# stm32_schematic.net
KiCad netlist of a schematic drawn in Altium Designer
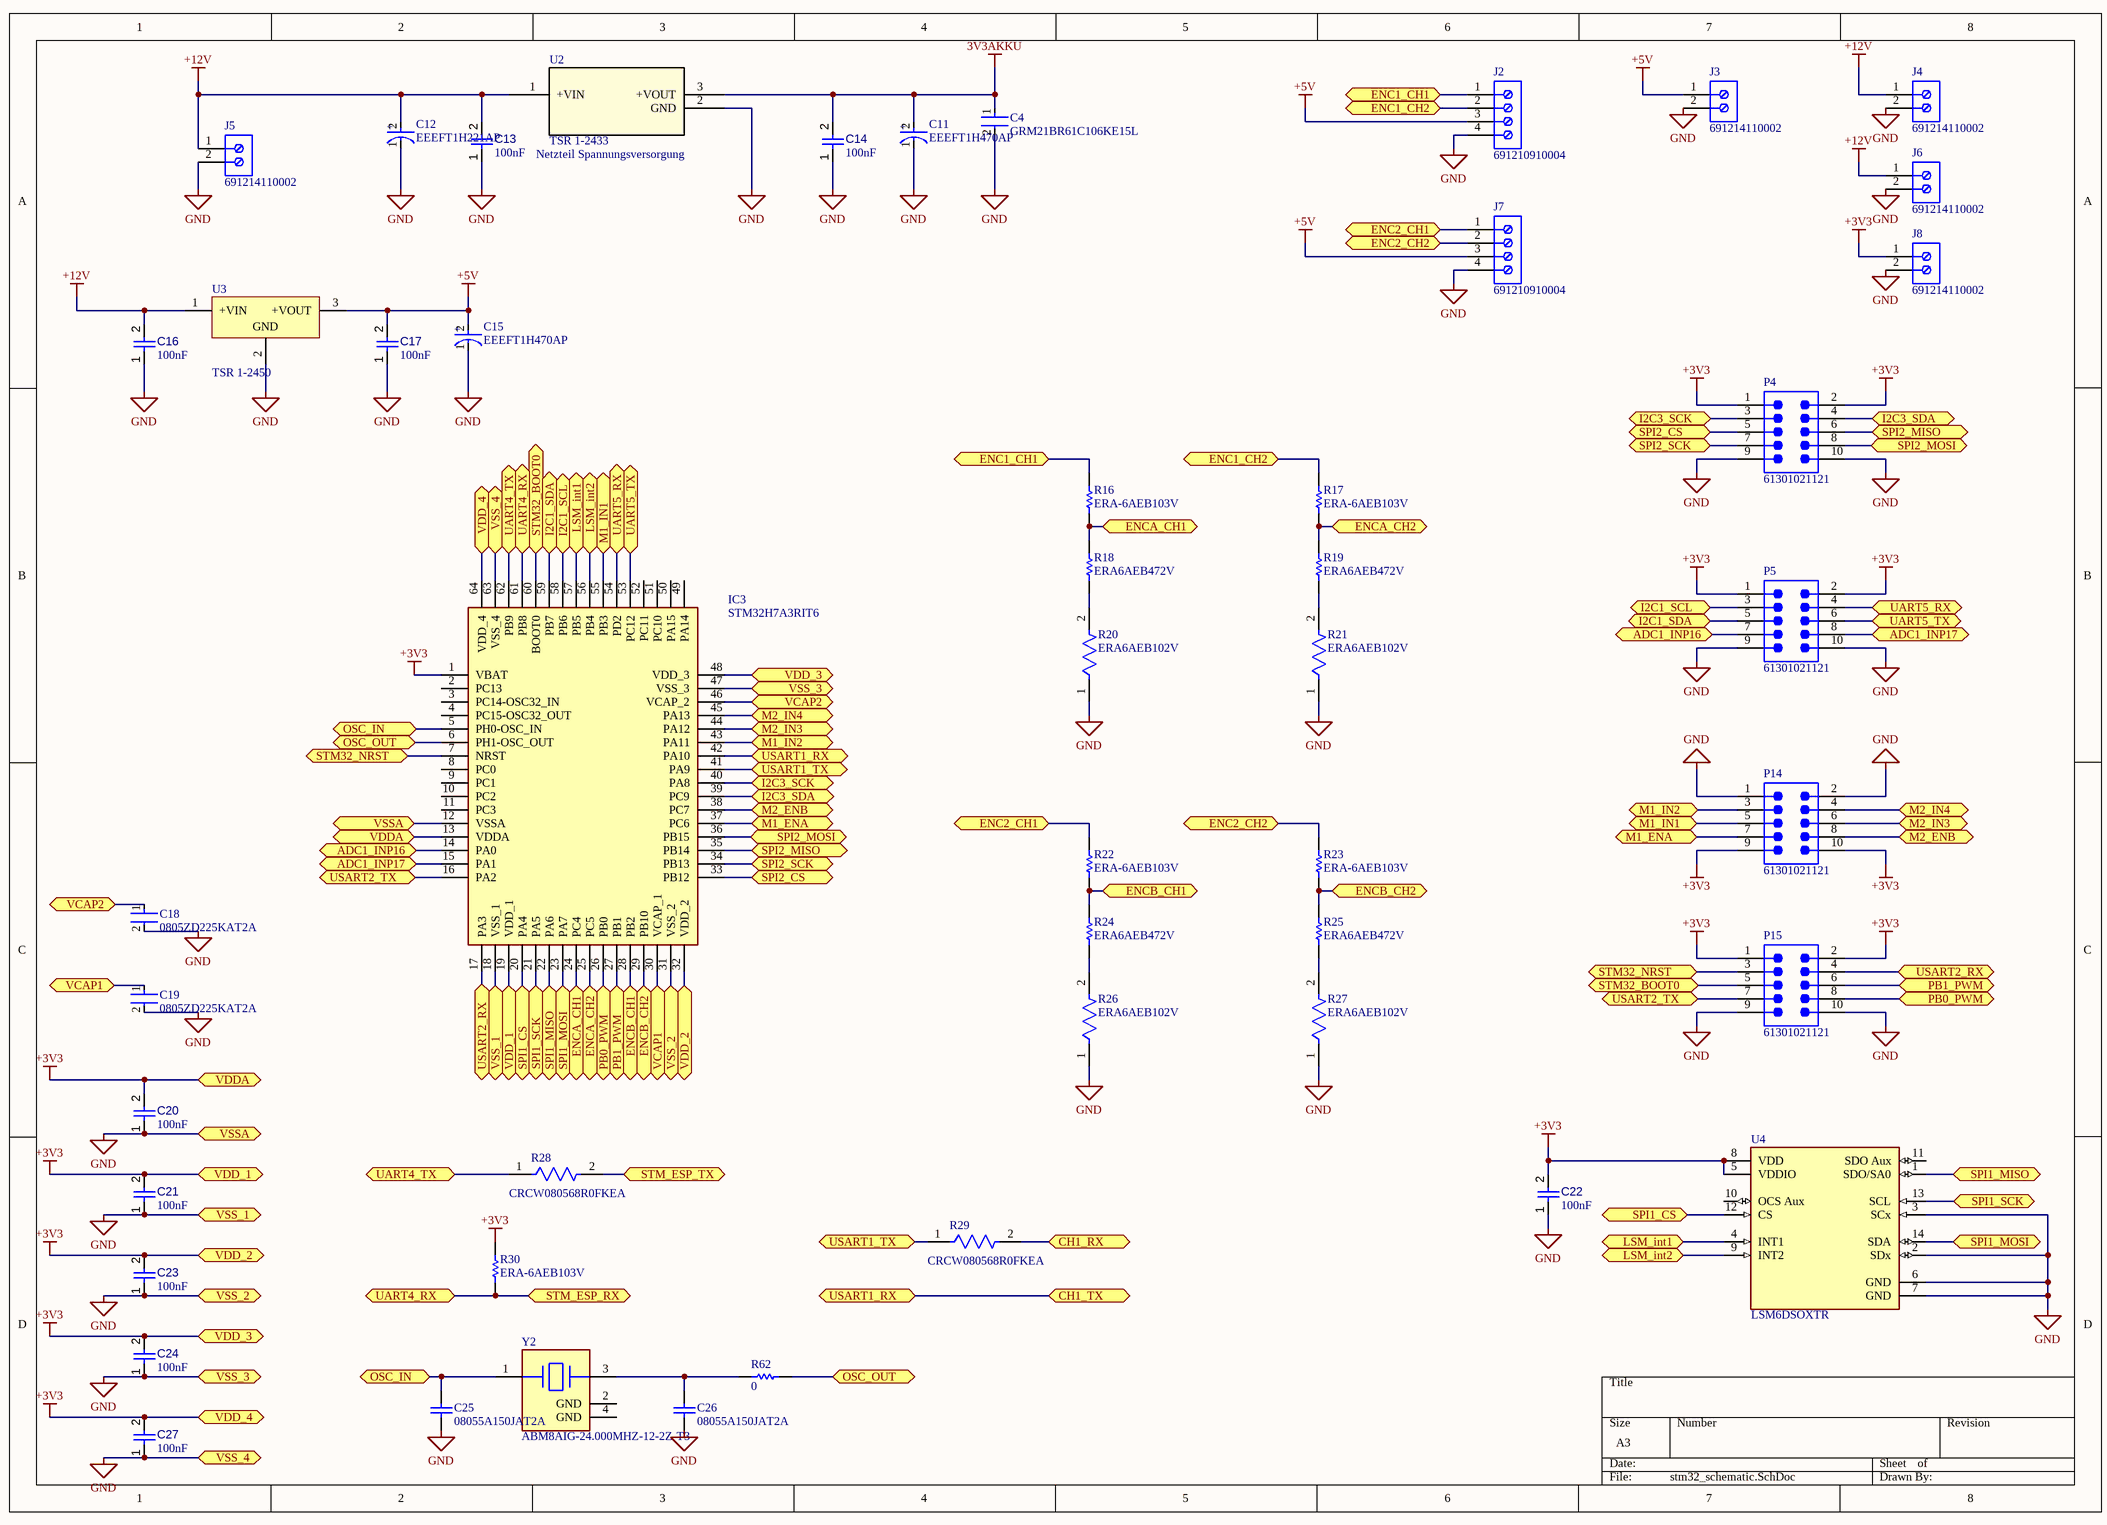
[diagram p0: stm32_schematic.SchDoc]

(export (version "E")
  (design (tool "Eeschema 10.0.6"))
  (components
    (comp (ref "C4")
      (value "GRM21BR61C106KE15L")
      (footprint "FP-GRM21B-0_1-IPC_C")
      (description "Chip Multilayer Ceramic Capacitors for General Purpose, 0805, 10uF, X5R, 15%, 10%, 16V")
      (fields (field (name "TOLERANCE") "10%") (field (name "VOLTAGE") "16V"))
      (libsource (lib "Altium Content Vault") (part "b4654b650e69147ec39a6b967a45e02"))
    )
    (comp (ref "C11")
      (value "EEEFT1H470AP")
      (footprint "FP-FTD-MFG")
      (description "CAP ALUM 47UF 20% 50V SMD")
      (fields (field (name "VOLTAGE") "50V") (field (name "TOLERANCE") "20%"))
      (libsource (lib "Altium Content Vault") (part "a00bbbee19879c290e62620ae7e47b1"))
    )
    (comp (ref "C12")
      (value "EEEFT1H221AP")
      (footprint "FP-FTF-MFG")
      (description "CAP ALUM 220UF 20% 50V SMD")
      (fields (field (name "TOLERANCE") "20%") (field (name "VOLTAGE") "50V"))
      (libsource (lib "Altium Content Vault") (part "203bc49f2ac43e59fd269a8c329ed05"))
    )
    (comp (ref "C13")
      (value "100nF")
      (footprint "CAPC2013X95X50LL10T25")
      (description "Chip Capacitor, 100 nF, +/- 10%, 50 V, 0805 (2012 Metric)")
      (fields (field (name "TOLERANCE") "10%") (field (name "Comment") "Capacitor 100 nF +/-10% 50 V 0805"))
      (libsource (lib "Lennart Götz") (part "CAP-NP-2"))
    )
    (comp (ref "C14")
      (value "100nF")
      (footprint "CAPC2013X95X50LL10T25")
      (description "Chip Capacitor, 100 nF, +/- 10%, 50 V, 0805 (2012 Metric)")
      (fields (field (name "TOLERANCE") "10%") (field (name "Comment") "Capacitor 100 nF +/-10% 50 V 0805"))
      (libsource (lib "Lennart Götz") (part "CAP-NP-2"))
    )
    (comp (ref "C15")
      (value "EEEFT1H470AP")
      (footprint "FP-FTD-MFG")
      (description "CAP ALUM 47UF 20% 50V SMD")
      (fields (field (name "VOLTAGE") "50V") (field (name "TOLERANCE") "20%"))
      (libsource (lib "Altium Content Vault") (part "a00bbbee19879c290e62620ae7e47b1"))
    )
    (comp (ref "C16")
      (value "100nF")
      (footprint "CAPC2013X95X50LL10T25")
      (description "Chip Capacitor, 100 nF, +/- 10%, 50 V, 0805 (2012 Metric)")
      (fields (field (name "TOLERANCE") "10%") (field (name "Comment") "Capacitor 100 nF +/-10% 50 V 0805"))
      (libsource (lib "Lennart Götz") (part "CAP-NP-2"))
    )
    (comp (ref "C17")
      (value "100nF")
      (footprint "CAPC2013X95X50LL10T25")
      (description "Chip Capacitor, 100 nF, +/- 10%, 50 V, 0805 (2012 Metric)")
      (fields (field (name "TOLERANCE") "10%") (field (name "Comment") "Capacitor 100 nF +/-10% 50 V 0805"))
      (libsource (lib "Lennart Götz") (part "CAP-NP-2"))
    )
    (comp (ref "C18")
      (value "0805ZD225KAT2A")
      (footprint "FP-0805-L_2_01_0_2-W_1_25-IPC_B")
      (description "General Purpose Ceramic Capacitor, 0805, 2.2uF, 10%, X5R, 15%, 10V")
      (fields (field (name "VOLTAGE") "10V") (field (name "TOLERANCE") "10%"))
      (libsource (lib "Altium Content Vault") (part "b4654b650e69147ec39a6b967a45e02"))
    )
    (comp (ref "C19")
      (value "0805ZD225KAT2A")
      (footprint "FP-0805-L_2_01_0_2-W_1_25-IPC_B")
      (description "General Purpose Ceramic Capacitor, 0805, 2.2uF, 10%, X5R, 15%, 10V")
      (fields (field (name "VOLTAGE") "10V") (field (name "TOLERANCE") "10%"))
      (libsource (lib "Altium Content Vault") (part "b4654b650e69147ec39a6b967a45e02"))
    )
    (comp (ref "C20")
      (value "100nF")
      (footprint "CAPC2013X95X50LL10T25")
      (description "Chip Capacitor, 100 nF, +/- 10%, 50 V, 0805 (2012 Metric)")
      (fields (field (name "TOLERANCE") "10%") (field (name "Comment") "Capacitor 100 nF +/-10% 50 V 0805"))
      (libsource (lib "Lennart Götz") (part "CAP-NP-2"))
    )
    (comp (ref "C21")
      (value "100nF")
      (footprint "CAPC2013X95X50LL10T25")
      (description "Chip Capacitor, 100 nF, +/- 10%, 50 V, 0805 (2012 Metric)")
      (fields (field (name "TOLERANCE") "10%") (field (name "Comment") "Capacitor 100 nF +/-10% 50 V 0805"))
      (libsource (lib "Lennart Götz") (part "CAP-NP-2"))
    )
    (comp (ref "C22")
      (value "100nF")
      (footprint "CAPC2013X95X50LL10T25")
      (description "Chip Capacitor, 100 nF, +/- 10%, 50 V, 0805 (2012 Metric)")
      (fields (field (name "TOLERANCE") "10%") (field (name "Comment") "Capacitor 100 nF +/-10% 50 V 0805"))
      (libsource (lib "Lennart Götz") (part "CAP-NP-2"))
    )
    (comp (ref "C23")
      (value "100nF")
      (footprint "CAPC2013X95X50LL10T25")
      (description "Chip Capacitor, 100 nF, +/- 10%, 50 V, 0805 (2012 Metric)")
      (fields (field (name "TOLERANCE") "10%") (field (name "Comment") "Capacitor 100 nF +/-10% 50 V 0805"))
      (libsource (lib "Lennart Götz") (part "CAP-NP-2"))
    )
    (comp (ref "C24")
      (value "100nF")
      (footprint "CAPC2013X95X50LL10T25")
      (description "Chip Capacitor, 100 nF, +/- 10%, 50 V, 0805 (2012 Metric)")
      (fields (field (name "TOLERANCE") "10%") (field (name "Comment") "Capacitor 100 nF +/-10% 50 V 0805"))
      (libsource (lib "Lennart Götz") (part "CAP-NP-2"))
    )
    (comp (ref "C25")
      (value "08055A150JAT2A")
      (footprint "CAPC2013X140X50LL20T25")
      (fields (field (name "MANUFACTURER") "AVX Interconnect / Elco"))
      (libsource (lib "Altium Content Vault") (part "CAP"))
    )
    (comp (ref "C26")
      (value "08055A150JAT2A")
      (footprint "CAPC2013X140X50LL20T25")
      (fields (field (name "MANUFACTURER") "AVX Interconnect / Elco"))
      (libsource (lib "Altium Content Vault") (part "CAP"))
    )
    (comp (ref "C27")
      (value "100nF")
      (footprint "CAPC2013X95X50LL10T25")
      (description "Chip Capacitor, 100 nF, +/- 10%, 50 V, 0805 (2012 Metric)")
      (fields (field (name "TOLERANCE") "10%") (field (name "Comment") "Capacitor 100 nF +/-10% 50 V 0805"))
      (libsource (lib "Lennart Götz") (part "CAP-NP-2"))
    )
    (comp (ref "IC3")
      (value "STM32H7A3RIT6")
      (footprint "SamacSys:QFP50P1200X1200X160-64N")
      (description "Integrated Circuit")
      (fields (field (name "MOUSER PART NUMBER") "511-STM32H7A3RIT6"))
      (libsource (lib "*") (part "STM32H7A3RIT6"))
    )
    (comp (ref "J2")
      (value "691210910004")
      (footprint "691210910004")
      (libsource (lib "Altium Content Vault") (part "TBL - 1R - 04P - Screw"))
    )
    (comp (ref "J3")
      (value "691214110002")
      (footprint "691214110002")
      (fields (field (name "VOLTAGE") "300V"))
      (libsource (lib "Altium Content Vault") (part "TBL - 1R - 02P - Screw"))
    )
    (comp (ref "J4")
      (value "691214110002")
      (footprint "691214110002")
      (fields (field (name "VOLTAGE") "300V"))
      (libsource (lib "Altium Content Vault") (part "TBL - 1R - 02P - Screw"))
    )
    (comp (ref "J5")
      (value "691214110002")
      (footprint "691214110002")
      (fields (field (name "VOLTAGE") "300V"))
      (libsource (lib "Altium Content Vault") (part "TBL - 1R - 02P - Screw"))
    )
    (comp (ref "J6")
      (value "691214110002")
      (footprint "691214110002")
      (fields (field (name "VOLTAGE") "300V"))
      (libsource (lib "Altium Content Vault") (part "TBL - 1R - 02P - Screw"))
    )
    (comp (ref "J7")
      (value "691210910004")
      (footprint "691210910004")
      (libsource (lib "Altium Content Vault") (part "TBL - 1R - 04P - Screw"))
    )
    (comp (ref "J8")
      (value "691214110002")
      (footprint "691214110002")
      (fields (field (name "VOLTAGE") "300V"))
      (libsource (lib "Altium Content Vault") (part "TBL - 1R - 02P - Screw"))
    )
    (comp (ref "P4")
      (value "61301021121")
      (footprint "61301021121")
      (libsource (lib "Altium Content Vault") (part "Header_Male_2R_10P"))
    )
    (comp (ref "P5")
      (value "61301021121")
      (footprint "61301021121")
      (libsource (lib "Altium Content Vault") (part "Header_Male_2R_10P"))
    )
    (comp (ref "P14")
      (value "61301021121")
      (footprint "61301021121")
      (libsource (lib "Altium Content Vault") (part "Header_Male_2R_10P"))
    )
    (comp (ref "P15")
      (value "61301021121")
      (footprint "61301021121")
      (libsource (lib "Altium Content Vault") (part "Header_Male_2R_10P"))
    )
    (comp (ref "R16")
      (value "ERA-6AEB103V")
      (footprint "RESC2013X60X40LL20T25_A")
      (fields (field (name "TOLERANCE") "0.1%") (field (name "MANUFACTURER") "Panasonic"))
      (libsource (lib "Altium Content Vault") (part "RES-2"))
    )
    (comp (ref "R17")
      (value "ERA-6AEB103V")
      (footprint "RESC2013X60X40LL20T25_A")
      (fields (field (name "TOLERANCE") "0.1%") (field (name "MANUFACTURER") "Panasonic"))
      (libsource (lib "Altium Content Vault") (part "RES-2"))
    )
    (comp (ref "R18")
      (value "ERA6AEB472V")
      (footprint "RESC2013X60X40ML20T25")
      (fields (field (name "MANUFACTURER") "Panasonic"))
      (libsource (lib "Altium Content Vault") (part "RES"))
    )
    (comp (ref "R19")
      (value "ERA6AEB472V")
      (footprint "RESC2013X60X40ML20T25")
      (fields (field (name "MANUFACTURER") "Panasonic"))
      (libsource (lib "Altium Content Vault") (part "RES"))
    )
    (comp (ref "R20")
      (value "ERA6AEB102V")
      (footprint "FP-ERA6A-IPC_C")
      (description "RES 1K OHM 0.1% 1/8W 0805")
      (fields (field (name "TOLERANCE") "0.1%"))
      (libsource (lib "Altium Content Vault") (part "1029c3af85768c4190bb7ad29bc67b5"))
    )
    (comp (ref "R21")
      (value "ERA6AEB102V")
      (footprint "FP-ERA6A-IPC_C")
      (description "RES 1K OHM 0.1% 1/8W 0805")
      (fields (field (name "TOLERANCE") "0.1%"))
      (libsource (lib "Altium Content Vault") (part "1029c3af85768c4190bb7ad29bc67b5"))
    )
    (comp (ref "R22")
      (value "ERA-6AEB103V")
      (footprint "RESC2013X60X40LL20T25_A")
      (fields (field (name "TOLERANCE") "0.1%") (field (name "MANUFACTURER") "Panasonic"))
      (libsource (lib "Altium Content Vault") (part "RES-2"))
    )
    (comp (ref "R23")
      (value "ERA-6AEB103V")
      (footprint "RESC2013X60X40LL20T25_A")
      (fields (field (name "TOLERANCE") "0.1%") (field (name "MANUFACTURER") "Panasonic"))
      (libsource (lib "Altium Content Vault") (part "RES-2"))
    )
    (comp (ref "R24")
      (value "ERA6AEB472V")
      (footprint "RESC2013X60X40ML20T25")
      (fields (field (name "MANUFACTURER") "Panasonic"))
      (libsource (lib "Altium Content Vault") (part "RES"))
    )
    (comp (ref "R25")
      (value "ERA6AEB472V")
      (footprint "RESC2013X60X40ML20T25")
      (fields (field (name "MANUFACTURER") "Panasonic"))
      (libsource (lib "Altium Content Vault") (part "RES"))
    )
    (comp (ref "R26")
      (value "ERA6AEB102V")
      (footprint "FP-ERA6A-IPC_C")
      (description "RES 1K OHM 0.1% 1/8W 0805")
      (fields (field (name "TOLERANCE") "0.1%"))
      (libsource (lib "Altium Content Vault") (part "1029c3af85768c4190bb7ad29bc67b5"))
    )
    (comp (ref "R27")
      (value "ERA6AEB102V")
      (footprint "FP-ERA6A-IPC_C")
      (description "RES 1K OHM 0.1% 1/8W 0805")
      (fields (field (name "TOLERANCE") "0.1%"))
      (libsource (lib "Altium Content Vault") (part "1029c3af85768c4190bb7ad29bc67b5"))
    )
    (comp (ref "R28")
      (value "CRCW080568R0FKEA")
      (footprint "FP-CRCW0805-e3-IPC_C")
      (description "RES Thick Film, 68Ω, 1%, 0.125W, 100ppm/°C, 0805")
      (fields (field (name "TOLERANCE") "1%"))
      (libsource (lib "Altium Content Vault") (part "1029c3af85768c4190bb7ad29bc67b5"))
    )
    (comp (ref "R29")
      (value "CRCW080568R0FKEA")
      (footprint "FP-CRCW0805-e3-IPC_C")
      (description "RES Thick Film, 68Ω, 1%, 0.125W, 100ppm/°C, 0805")
      (fields (field (name "TOLERANCE") "1%"))
      (libsource (lib "Altium Content Vault") (part "1029c3af85768c4190bb7ad29bc67b5"))
    )
    (comp (ref "R30")
      (value "ERA-6AEB103V")
      (footprint "RESC2013X60X40LL20T25_A")
      (fields (field (name "TOLERANCE") "0.1%") (field (name "MANUFACTURER") "Panasonic"))
      (libsource (lib "Altium Content Vault") (part "RES-2"))
    )
    (comp (ref "R62")
      (value "0")
      (footprint "RESC2013X60X35ML10T20")
      (description "Chip Resistor, 0 Ohm, 0.125 W, -55 to 155 degC, 0805 (2012 Metric)")
      (fields (field (name "POWER") "125mW") (field (name "TOLERANCE") "5%"))
      (libsource (lib "Lennart Götz") (part "RES-2"))
    )
    (comp (ref "U2")
      (value "TSR 1-2433")
      (footprint "TSR1-SINGLE_TRP")
      (libsource (lib "Altium Content Vault") (part "TSR 1-2433"))
    )
    (comp (ref "U3")
      (value "TSR 1-2450")
      (footprint "TRACO-SIP-3_V")
      (description "DC/DC converter, 5 VDC, 1000 mA, -40 to 85 degC, 3-Pin SIP, RoHS")
      (fields (field (name "MANUFACTURER") "Tracopower"))
      (libsource (lib "Altium Content Vault") (part "TRACO-TSR1-2450-SIP-3"))
    )
    (comp (ref "U4")
      (value "LSM6DSOXTR")
      (footprint "FP-LGA-14L-DM00249496-MFG")
      (description "INEMO INERTIAL MODULE: 3D ACCELE")
      (fields
        (field (name "OCTOPART") "https://octopart.com/lsm6dsoxtr-stmicroelectronics-98102600")
        (field (name "MANUFACTURER") "STMicroelectronics")
      )
      (libsource (lib "Altium Content Vault") (part "e907d670a73553dd54601dfd5d274f3"))
    )
    (comp (ref "Y2")
      (value "ABM8AIG-24.000MHZ-12-2Z-T3")
      (footprint "FP-ABM8AIG-MFG")
      (description "Crystal 24MHz ±20ppm (Tol) ±50ppm (Stability) 12pF FUND 50Ω Automotive 4-Pin Ultra Mini-CSMD T/R")
      (libsource (lib "Altium Content Vault") (part "5645ab55de99a04feaa93ac4102b7fe"))
    )
  )
  (nets
    (net (code "1") (name "+3V3") (class "Default")
      (node (ref "C20") (pin "2") (pinfunction "2_2") (pintype "passive"))
      (node (ref "C21") (pin "2") (pinfunction "2_2") (pintype "passive"))
      (node (ref "C22") (pin "2") (pinfunction "2_2") (pintype "passive"))
      (node (ref "C23") (pin "2") (pinfunction "2_2") (pintype "passive"))
      (node (ref "C24") (pin "2") (pinfunction "2_2") (pintype "passive"))
      (node (ref "C27") (pin "2") (pinfunction "2_2") (pintype "passive"))
      (node (ref "IC3") (pin "1") (pinfunction "VBAT_1") (pintype "passive"))
      (node (ref "IC3") (pin "13") (pinfunction "VDDA_13") (pintype "passive"))
      (node (ref "IC3") (pin "19") (pinfunction "VDD_1_19") (pintype "passive"))
      (node (ref "IC3") (pin "32") (pinfunction "VDD_2_32") (pintype "passive"))
      (node (ref "IC3") (pin "48") (pinfunction "VDD_3_48") (pintype "passive"))
      (node (ref "IC3") (pin "64") (pinfunction "VDD_4_64") (pintype "passive"))
      (node (ref "J8") (pin "1") (pinfunction "1_1") (pintype "passive"))
      (node (ref "P14") (pin "10") (pinfunction "10_10") (pintype "passive"))
      (node (ref "P14") (pin "9") (pinfunction "9_9") (pintype "passive"))
      (node (ref "P15") (pin "1") (pinfunction "1_1") (pintype "passive"))
      (node (ref "P15") (pin "2") (pinfunction "2_2") (pintype "passive"))
      (node (ref "P4") (pin "1") (pinfunction "1_1") (pintype "passive"))
      (node (ref "P4") (pin "2") (pinfunction "2_2") (pintype "passive"))
      (node (ref "P5") (pin "1") (pinfunction "1_1") (pintype "passive"))
      (node (ref "P5") (pin "2") (pinfunction "2_2") (pintype "passive"))
      (node (ref "R30") (pin "2") (pinfunction "2_2") (pintype "passive"))
      (node (ref "U4") (pin "5") (pinfunction "VDDIO_5") (pintype "power_in"))
      (node (ref "U4") (pin "8") (pinfunction "VDD_8") (pintype "power_in"))
    )
    (net (code "2") (name "+5V") (class "Default")
      (node (ref "C15") (pin "2") (pinfunction "A_2") (pintype "passive"))
      (node (ref "C17") (pin "2") (pinfunction "2_2") (pintype "passive"))
      (node (ref "J2") (pin "3") (pinfunction "3_3") (pintype "passive"))
      (node (ref "J3") (pin "1") (pinfunction "1_1") (pintype "passive"))
      (node (ref "J7") (pin "3") (pinfunction "3_3") (pintype "passive"))
      (node (ref "U3") (pin "3") (pinfunction "+VOUT_3") (pintype "power_in"))
    )
    (net (code "3") (name "+12V") (class "Default")
      (node (ref "C12") (pin "2") (pinfunction "A_2") (pintype "passive"))
      (node (ref "C13") (pin "2") (pinfunction "2_2") (pintype "passive"))
      (node (ref "C16") (pin "2") (pinfunction "2_2") (pintype "passive"))
      (node (ref "J4") (pin "1") (pinfunction "1_1") (pintype "passive"))
      (node (ref "J5") (pin "1") (pinfunction "1_1") (pintype "passive"))
      (node (ref "J6") (pin "1") (pinfunction "1_1") (pintype "passive"))
      (node (ref "U2") (pin "1") (pinfunction "+VIN_1") (pintype "power_in"))
      (node (ref "U3") (pin "1") (pinfunction "+VIN_1") (pintype "power_in"))
    )
    (net (code "4") (name "/ADC1_INP16") (class "Default")
      (node (ref "IC3") (pin "14") (pinfunction "PA0_14") (pintype "passive"))
      (node (ref "P5") (pin "7") (pinfunction "7_7") (pintype "passive"))
    )
    (net (code "5") (name "/ADC1_INP17") (class "Default")
      (node (ref "IC3") (pin "15") (pinfunction "PA1_15") (pintype "passive"))
      (node (ref "P5") (pin "8") (pinfunction "8_8") (pintype "passive"))
    )
    (net (code "6") (name "/CH1_RX") (class "Default")
      (node (ref "R29") (pin "2") (pinfunction "2_2") (pintype "passive"))
    )
    (net (code "7") (name "/CH1_TX") (class "Default")
      (node (ref "IC3") (pin "42") (pinfunction "PA10_42") (pintype "passive"))
    )
    (net (code "8") (name "/ENC1_CH1") (class "Default")
      (node (ref "J2") (pin "1") (pinfunction "1_1") (pintype "passive"))
      (node (ref "R16") (pin "2") (pinfunction "2_2") (pintype "passive"))
    )
    (net (code "9") (name "/ENC1_CH2") (class "Default")
      (node (ref "J2") (pin "2") (pinfunction "2_2") (pintype "passive"))
      (node (ref "R17") (pin "2") (pinfunction "2_2") (pintype "passive"))
    )
    (net (code "10") (name "/ENC2_CH1") (class "Default")
      (node (ref "J7") (pin "1") (pinfunction "1_1") (pintype "passive"))
      (node (ref "R22") (pin "2") (pinfunction "2_2") (pintype "passive"))
    )
    (net (code "11") (name "/ENC2_CH2") (class "Default")
      (node (ref "J7") (pin "2") (pinfunction "2_2") (pintype "passive"))
      (node (ref "R23") (pin "2") (pinfunction "2_2") (pintype "passive"))
    )
    (net (code "12") (name "/ENCA_CH1") (class "Default")
      (node (ref "IC3") (pin "24") (pinfunction "PC4_24") (pintype "passive"))
      (node (ref "R16") (pin "1") (pinfunction "1_1") (pintype "passive"))
      (node (ref "R18") (pin "2") (pinfunction "2_2") (pintype "passive"))
    )
    (net (code "13") (name "/ENCA_CH2") (class "Default")
      (node (ref "IC3") (pin "25") (pinfunction "PC5_25") (pintype "passive"))
      (node (ref "R17") (pin "1") (pinfunction "1_1") (pintype "passive"))
      (node (ref "R19") (pin "2") (pinfunction "2_2") (pintype "passive"))
    )
    (net (code "14") (name "/ENCB_CH1") (class "Default")
      (node (ref "IC3") (pin "28") (pinfunction "PB2_28") (pintype "passive"))
      (node (ref "R22") (pin "1") (pinfunction "1_1") (pintype "passive"))
      (node (ref "R24") (pin "2") (pinfunction "2_2") (pintype "passive"))
    )
    (net (code "15") (name "/ENCB_CH2") (class "Default")
      (node (ref "IC3") (pin "29") (pinfunction "PB10_29") (pintype "passive"))
      (node (ref "R23") (pin "1") (pinfunction "1_1") (pintype "passive"))
      (node (ref "R25") (pin "2") (pinfunction "2_2") (pintype "passive"))
    )
    (net (code "16") (name "/I2C1_SCL") (class "Default")
      (node (ref "IC3") (pin "58") (pinfunction "PB6_58") (pintype "passive"))
      (node (ref "P5") (pin "3") (pinfunction "3_3") (pintype "passive"))
    )
    (net (code "17") (name "/I2C1_SDA") (class "Default")
      (node (ref "IC3") (pin "59") (pinfunction "PB7_59") (pintype "passive"))
      (node (ref "P5") (pin "5") (pinfunction "5_5") (pintype "passive"))
    )
    (net (code "18") (name "/I2C3_SCK") (class "Default")
      (node (ref "IC3") (pin "40") (pinfunction "PA8_40") (pintype "passive"))
      (node (ref "P4") (pin "3") (pinfunction "3_3") (pintype "passive"))
    )
    (net (code "19") (name "/I2C3_SDA") (class "Default")
      (node (ref "IC3") (pin "39") (pinfunction "PC9_39") (pintype "passive"))
      (node (ref "P4") (pin "4") (pinfunction "4_4") (pintype "passive"))
    )
    (net (code "20") (name "/LSM_int1") (class "Default")
      (node (ref "IC3") (pin "57") (pinfunction "PB5_57") (pintype "passive"))
      (node (ref "U4") (pin "4") (pinfunction "INT1_4") (pintype "input"))
    )
    (net (code "21") (name "/LSM_int2") (class "Default")
      (node (ref "IC3") (pin "56") (pinfunction "PB4_56") (pintype "passive"))
      (node (ref "U4") (pin "9") (pinfunction "INT2_9") (pintype "input"))
    )
    (net (code "22") (name "/M1_ENA") (class "Default")
      (node (ref "IC3") (pin "37") (pinfunction "PC6_37") (pintype "passive"))
      (node (ref "P14") (pin "7") (pinfunction "7_7") (pintype "passive"))
    )
    (net (code "23") (name "/M1_IN1") (class "Default")
      (node (ref "IC3") (pin "55") (pinfunction "PB3_55") (pintype "passive"))
      (node (ref "P14") (pin "5") (pinfunction "5_5") (pintype "passive"))
    )
    (net (code "24") (name "/M1_IN2") (class "Default")
      (node (ref "IC3") (pin "43") (pinfunction "PA11_43") (pintype "passive"))
      (node (ref "P14") (pin "3") (pinfunction "3_3") (pintype "passive"))
    )
    (net (code "25") (name "/M2_ENB") (class "Default")
      (node (ref "IC3") (pin "38") (pinfunction "PC7_38") (pintype "passive"))
      (node (ref "P14") (pin "8") (pinfunction "8_8") (pintype "passive"))
    )
    (net (code "26") (name "/M2_IN3") (class "Default")
      (node (ref "IC3") (pin "44") (pinfunction "PA12_44") (pintype "passive"))
      (node (ref "P14") (pin "6") (pinfunction "6_6") (pintype "passive"))
    )
    (net (code "27") (name "/M2_IN4") (class "Default")
      (node (ref "IC3") (pin "45") (pinfunction "PA13_45") (pintype "passive"))
      (node (ref "P14") (pin "4") (pinfunction "4_4") (pintype "passive"))
    )
    (net (code "28") (name "/OSC_IN") (class "Default")
      (node (ref "C25") (pin "2") (pinfunction "2_2") (pintype "passive"))
      (node (ref "IC3") (pin "5") (pinfunction "PH0-OSC_IN_5") (pintype "passive"))
      (node (ref "Y2") (pin "1") (pinfunction "1_1") (pintype "passive"))
    )
    (net (code "29") (name "/OSC_OUT") (class "Default")
      (node (ref "IC3") (pin "6") (pinfunction "PH1-OSC_OUT_6") (pintype "passive"))
      (node (ref "R62") (pin "2") (pinfunction "2_2") (pintype "passive"))
    )
    (net (code "30") (name "/PB0_PWM") (class "Default")
      (node (ref "IC3") (pin "26") (pinfunction "PB0_26") (pintype "passive"))
      (node (ref "P15") (pin "8") (pinfunction "8_8") (pintype "passive"))
    )
    (net (code "31") (name "/PB1_PWM") (class "Default")
      (node (ref "IC3") (pin "27") (pinfunction "PB1_27") (pintype "passive"))
      (node (ref "P15") (pin "6") (pinfunction "6_6") (pintype "passive"))
    )
    (net (code "32") (name "/SPI1_CS") (class "Default")
      (node (ref "IC3") (pin "20") (pinfunction "PA4_20") (pintype "passive"))
      (node (ref "U4") (pin "12") (pinfunction "CS_12") (pintype "input"))
    )
    (net (code "33") (name "/SPI1_MISO") (class "Default")
      (node (ref "IC3") (pin "22") (pinfunction "PA6_22") (pintype "passive"))
      (node (ref "U4") (pin "1") (pinfunction "SDO/SA0_1") (pintype "bidirectional"))
    )
    (net (code "34") (name "/SPI1_MOSI") (class "Default")
      (node (ref "IC3") (pin "23") (pinfunction "PA7_23") (pintype "passive"))
      (node (ref "U4") (pin "14") (pinfunction "SDA_14") (pintype "bidirectional"))
    )
    (net (code "35") (name "/SPI1_SCK") (class "Default")
      (node (ref "IC3") (pin "21") (pinfunction "PA5_21") (pintype "passive"))
      (node (ref "U4") (pin "13") (pinfunction "SCL_13") (pintype "input"))
    )
    (net (code "36") (name "/SPI2_CS") (class "Default")
      (node (ref "IC3") (pin "33") (pinfunction "PB12_33") (pintype "passive"))
      (node (ref "P4") (pin "5") (pinfunction "5_5") (pintype "passive"))
    )
    (net (code "37") (name "/SPI2_MISO") (class "Default")
      (node (ref "IC3") (pin "35") (pinfunction "PB14_35") (pintype "passive"))
      (node (ref "P4") (pin "6") (pinfunction "6_6") (pintype "passive"))
    )
    (net (code "38") (name "/SPI2_MOSI") (class "Default")
      (node (ref "IC3") (pin "36") (pinfunction "PB15_36") (pintype "passive"))
      (node (ref "P4") (pin "8") (pinfunction "8_8") (pintype "passive"))
    )
    (net (code "39") (name "/SPI2_SCK") (class "Default")
      (node (ref "IC3") (pin "34") (pinfunction "PB13_34") (pintype "passive"))
      (node (ref "P4") (pin "7") (pinfunction "7_7") (pintype "passive"))
    )
    (net (code "40") (name "/STM32_BOOT0") (class "Default")
      (node (ref "IC3") (pin "60") (pinfunction "BOOT0_60") (pintype "passive"))
      (node (ref "P15") (pin "5") (pinfunction "5_5") (pintype "passive"))
    )
    (net (code "41") (name "/STM32_NRST") (class "Default")
      (node (ref "IC3") (pin "7") (pinfunction "NRST_7") (pintype "passive"))
      (node (ref "P15") (pin "3") (pinfunction "3_3") (pintype "passive"))
    )
    (net (code "42") (name "/STM_ESP_RX") (class "Default")
      (node (ref "IC3") (pin "61") (pinfunction "PB8_61") (pintype "passive"))
      (node (ref "R30") (pin "1") (pinfunction "1_1") (pintype "passive"))
    )
    (net (code "43") (name "/STM_ESP_TX") (class "Default")
      (node (ref "R28") (pin "2") (pinfunction "2_2") (pintype "passive"))
    )
    (net (code "44") (name "/UART4_TX") (class "Default")
      (node (ref "IC3") (pin "62") (pinfunction "PB9_62") (pintype "passive"))
      (node (ref "R28") (pin "1") (pinfunction "1_1") (pintype "passive"))
    )
    (net (code "45") (name "/UART5_RX") (class "Default")
      (node (ref "IC3") (pin "54") (pinfunction "PD2_54") (pintype "passive"))
      (node (ref "P5") (pin "4") (pinfunction "4_4") (pintype "passive"))
    )
    (net (code "46") (name "/UART5_TX") (class "Default")
      (node (ref "IC3") (pin "53") (pinfunction "PC12_53") (pintype "passive"))
      (node (ref "P5") (pin "6") (pinfunction "6_6") (pintype "passive"))
    )
    (net (code "47") (name "/USART1_TX") (class "Default")
      (node (ref "IC3") (pin "41") (pinfunction "PA9_41") (pintype "passive"))
      (node (ref "R29") (pin "1") (pinfunction "1_1") (pintype "passive"))
    )
    (net (code "48") (name "/USART2_RX") (class "Default")
      (node (ref "IC3") (pin "17") (pinfunction "PA3_17") (pintype "passive"))
      (node (ref "P15") (pin "4") (pinfunction "4_4") (pintype "passive"))
    )
    (net (code "49") (name "/USART2_TX") (class "Default")
      (node (ref "IC3") (pin "16") (pinfunction "PA2_16") (pintype "passive"))
      (node (ref "P15") (pin "7") (pinfunction "7_7") (pintype "passive"))
    )
    (net (code "50") (name "/VCAP1") (class "Default")
      (node (ref "C19") (pin "1") (pinfunction "1_1") (pintype "passive"))
      (node (ref "IC3") (pin "30") (pinfunction "VCAP_1_30") (pintype "passive"))
    )
    (net (code "51") (name "/VCAP2") (class "Default")
      (node (ref "C18") (pin "1") (pinfunction "1_1") (pintype "passive"))
      (node (ref "IC3") (pin "46") (pinfunction "VCAP_2_46") (pintype "passive"))
    )
    (net (code "52") (name "3V3AKKU") (class "Default")
      (node (ref "C11") (pin "2") (pinfunction "A_2") (pintype "passive"))
      (node (ref "C14") (pin "2") (pinfunction "2_2") (pintype "passive"))
      (node (ref "C4") (pin "1") (pinfunction "1_1") (pintype "passive"))
      (node (ref "U2") (pin "3") (pinfunction "+VOUT_3") (pintype "power_in"))
    )
    (net (code "53") (name "GND") (class "Default")
      (node (ref "C11") (pin "1") (pinfunction "C_1") (pintype "passive"))
      (node (ref "C12") (pin "1") (pinfunction "C_1") (pintype "passive"))
      (node (ref "C13") (pin "1") (pinfunction "1_1") (pintype "passive"))
      (node (ref "C14") (pin "1") (pinfunction "1_1") (pintype "passive"))
      (node (ref "C15") (pin "1") (pinfunction "C_1") (pintype "passive"))
      (node (ref "C16") (pin "1") (pinfunction "1_1") (pintype "passive"))
      (node (ref "C17") (pin "1") (pinfunction "1_1") (pintype "passive"))
      (node (ref "C18") (pin "2") (pinfunction "2_2") (pintype "passive"))
      (node (ref "C19") (pin "2") (pinfunction "2_2") (pintype "passive"))
      (node (ref "C20") (pin "1") (pinfunction "1_1") (pintype "passive"))
      (node (ref "C21") (pin "1") (pinfunction "1_1") (pintype "passive"))
      (node (ref "C22") (pin "1") (pinfunction "1_1") (pintype "passive"))
      (node (ref "C23") (pin "1") (pinfunction "1_1") (pintype "passive"))
      (node (ref "C24") (pin "1") (pinfunction "1_1") (pintype "passive"))
      (node (ref "C25") (pin "1") (pinfunction "1_1") (pintype "passive"))
      (node (ref "C26") (pin "1") (pinfunction "1_1") (pintype "passive"))
      (node (ref "C27") (pin "1") (pinfunction "1_1") (pintype "passive"))
      (node (ref "C4") (pin "2") (pinfunction "2_2") (pintype "passive"))
      (node (ref "IC3") (pin "12") (pinfunction "VSSA_12") (pintype "passive"))
      (node (ref "IC3") (pin "18") (pinfunction "VSS_1_18") (pintype "passive"))
      (node (ref "IC3") (pin "31") (pinfunction "VSS_2_31") (pintype "passive"))
      (node (ref "IC3") (pin "47") (pinfunction "VSS_3_47") (pintype "passive"))
      (node (ref "IC3") (pin "63") (pinfunction "VSS_4_63") (pintype "passive"))
      (node (ref "J2") (pin "4") (pinfunction "4_4") (pintype "passive"))
      (node (ref "J3") (pin "2") (pinfunction "2_2") (pintype "passive"))
      (node (ref "J4") (pin "2") (pinfunction "2_2") (pintype "passive"))
      (node (ref "J5") (pin "2") (pinfunction "2_2") (pintype "passive"))
      (node (ref "J6") (pin "2") (pinfunction "2_2") (pintype "passive"))
      (node (ref "J7") (pin "4") (pinfunction "4_4") (pintype "passive"))
      (node (ref "J8") (pin "2") (pinfunction "2_2") (pintype "passive"))
      (node (ref "P14") (pin "1") (pinfunction "1_1") (pintype "passive"))
      (node (ref "P14") (pin "2") (pinfunction "2_2") (pintype "passive"))
      (node (ref "P15") (pin "10") (pinfunction "10_10") (pintype "passive"))
      (node (ref "P15") (pin "9") (pinfunction "9_9") (pintype "passive"))
      (node (ref "P4") (pin "10") (pinfunction "10_10") (pintype "passive"))
      (node (ref "P4") (pin "9") (pinfunction "9_9") (pintype "passive"))
      (node (ref "P5") (pin "10") (pinfunction "10_10") (pintype "passive"))
      (node (ref "P5") (pin "9") (pinfunction "9_9") (pintype "passive"))
      (node (ref "R20") (pin "1") (pinfunction "1_1") (pintype "passive"))
      (node (ref "R21") (pin "1") (pinfunction "1_1") (pintype "passive"))
      (node (ref "R26") (pin "1") (pinfunction "1_1") (pintype "passive"))
      (node (ref "R27") (pin "1") (pinfunction "1_1") (pintype "passive"))
      (node (ref "U2") (pin "2") (pinfunction "GND_2") (pintype "power_in"))
      (node (ref "U3") (pin "2") (pinfunction "GND_2") (pintype "power_in"))
      (node (ref "U4") (pin "2") (pinfunction "SDx_2") (pintype "bidirectional"))
      (node (ref "U4") (pin "3") (pinfunction "SCx_3") (pintype "input"))
      (node (ref "U4") (pin "6") (pinfunction "GND_6") (pintype "power_in"))
      (node (ref "U4") (pin "7") (pinfunction "GND_7") (pintype "power_in"))
    )
    (net (code "54") (name "Net-(C26-Pad2)") (class "Default")
      (node (ref "C26") (pin "2") (pinfunction "2_2") (pintype "passive"))
      (node (ref "R62") (pin "1") (pinfunction "1_1") (pintype "passive"))
      (node (ref "Y2") (pin "3") (pinfunction "3_3") (pintype "passive"))
    )
    (net (code "55") (name "Net-(R18-Pad1)") (class "Default")
      (node (ref "R18") (pin "1") (pinfunction "1_1") (pintype "passive"))
      (node (ref "R20") (pin "2") (pinfunction "2_2") (pintype "passive"))
    )
    (net (code "56") (name "Net-(R19-Pad1)") (class "Default")
      (node (ref "R19") (pin "1") (pinfunction "1_1") (pintype "passive"))
      (node (ref "R21") (pin "2") (pinfunction "2_2") (pintype "passive"))
    )
    (net (code "57") (name "Net-(R24-Pad1)") (class "Default")
      (node (ref "R24") (pin "1") (pinfunction "1_1") (pintype "passive"))
      (node (ref "R26") (pin "2") (pinfunction "2_2") (pintype "passive"))
    )
    (net (code "58") (name "Net-(R25-Pad1)") (class "Default")
      (node (ref "R25") (pin "1") (pinfunction "1_1") (pintype "passive"))
      (node (ref "R27") (pin "2") (pinfunction "2_2") (pintype "passive"))
    )
    (net (code "59") (name "unconnected-(IC3-PA14-Pad49)") (class "Default")
      (node (ref "IC3") (pin "49") (pinfunction "PA14_49") (pintype "passive"))
    )
    (net (code "60") (name "unconnected-(IC3-PA15-Pad50)") (class "Default")
      (node (ref "IC3") (pin "50") (pinfunction "PA15_50") (pintype "passive"))
    )
    (net (code "61") (name "unconnected-(IC3-PC0-Pad8)") (class "Default")
      (node (ref "IC3") (pin "8") (pinfunction "PC0_8") (pintype "passive"))
    )
    (net (code "62") (name "unconnected-(IC3-PC1-Pad9)") (class "Default")
      (node (ref "IC3") (pin "9") (pinfunction "PC1_9") (pintype "passive"))
    )
    (net (code "63") (name "unconnected-(IC3-PC2-Pad10)") (class "Default")
      (node (ref "IC3") (pin "10") (pinfunction "PC2_10") (pintype "passive"))
    )
    (net (code "64") (name "unconnected-(IC3-PC3-Pad11)") (class "Default")
      (node (ref "IC3") (pin "11") (pinfunction "PC3_11") (pintype "passive"))
    )
    (net (code "65") (name "unconnected-(IC3-PC10-Pad51)") (class "Default")
      (node (ref "IC3") (pin "51") (pinfunction "PC10_51") (pintype "passive"))
    )
    (net (code "66") (name "unconnected-(IC3-PC11-Pad52)") (class "Default")
      (node (ref "IC3") (pin "52") (pinfunction "PC11_52") (pintype "passive"))
    )
    (net (code "67") (name "unconnected-(IC3-PC13-Pad2)") (class "Default")
      (node (ref "IC3") (pin "2") (pinfunction "PC13_2") (pintype "passive"))
    )
    (net (code "68") (name "unconnected-(IC3-PC14-OSC32_IN-Pad3)") (class "Default")
      (node (ref "IC3") (pin "3") (pinfunction "PC14-OSC32_IN_3") (pintype "passive"))
    )
    (net (code "69") (name "unconnected-(IC3-PC15-OSC32_OUT-Pad4)") (class "Default")
      (node (ref "IC3") (pin "4") (pinfunction "PC15-OSC32_OUT_4") (pintype "passive"))
    )
    (net (code "70") (name "unconnected-(U4-OCS_Aux-Pad10)") (class "Default")
      (node (ref "U4") (pin "10") (pinfunction "OCS_Aux_10") (pintype "bidirectional"))
    )
    (net (code "71") (name "unconnected-(U4-SDO_Aux-Pad11)") (class "Default")
      (node (ref "U4") (pin "11") (pinfunction "SDO_Aux_11") (pintype "bidirectional"))
    )
    (net (code "72") (name "unconnected-(Y2-GND-Pad2)") (class "Default")
      (node (ref "Y2") (pin "2") (pinfunction "GND_2") (pintype "power_in"))
    )
    (net (code "73") (name "unconnected-(Y2-GND-Pad4)") (class "Default")
      (node (ref "Y2") (pin "4") (pinfunction "GND_4") (pintype "power_in"))
    )
  )
)
